# pcb-bldc-sensorless2.net
KiCad netlist of a schematic drawn in EAGLE
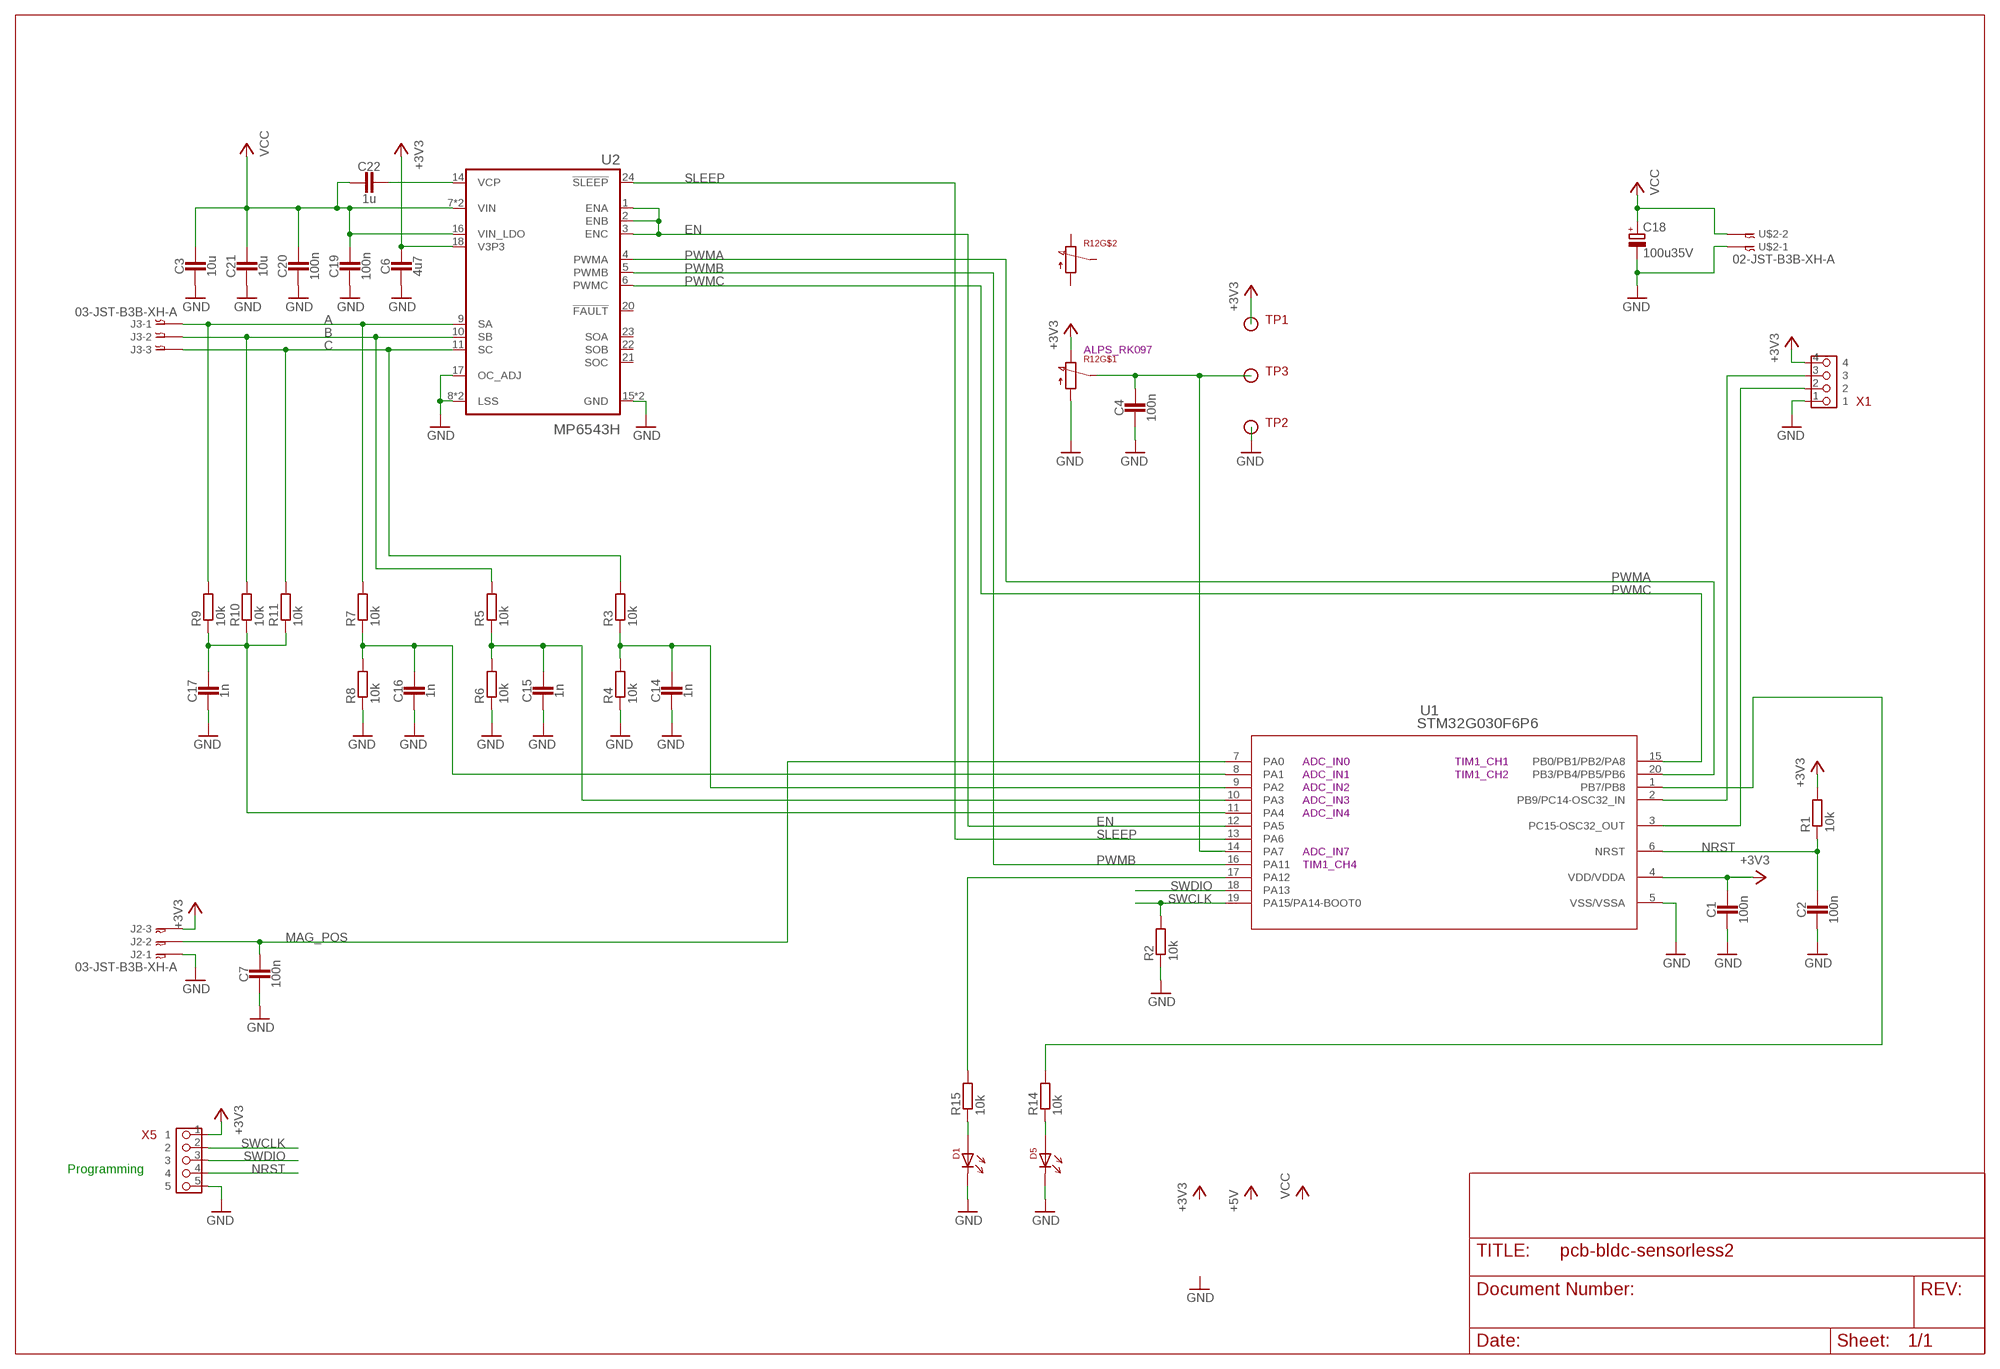
[diagram p0: schematic, sheet 1]

(export (version "E")
  (design (tool "Eeschema 10.0.6"))
  (components
    (comp (ref "C1")
      (value "100n")
      (footprint "eagle-import:0603_CAP")
      (libsource (lib "eagle-import") (part "CAPACITOR0603_CAP"))
    )
    (comp (ref "C2")
      (value "100n")
      (footprint "eagle-import:0603_CAP")
      (libsource (lib "eagle-import") (part "CAPACITOR0603_CAP"))
    )
    (comp (ref "C3")
      (value "10u")
      (footprint "eagle-import:1206_CAP")
      (libsource (lib "eagle-import") (part "CAPACITOR1206_CAP"))
    )
    (comp (ref "C4")
      (value "100n")
      (footprint "eagle-import:0603_CAP")
      (libsource (lib "eagle-import") (part "CAPACITOR0603_CAP"))
    )
    (comp (ref "C6")
      (value "4u7")
      (footprint "eagle-import:0805_CAP")
      (libsource (lib "eagle-import") (part "CAPACITOR0805_CAP"))
    )
    (comp (ref "C7")
      (value "100n")
      (footprint "eagle-import:0603_CAP")
      (libsource (lib "eagle-import") (part "CAPACITOR0603_CAP"))
    )
    (comp (ref "C14")
      (value "1n")
      (footprint "eagle-import:0603_CAP")
      (libsource (lib "eagle-import") (part "CAPACITOR0603_CAP"))
    )
    (comp (ref "C15")
      (value "1n")
      (footprint "eagle-import:0603_CAP")
      (libsource (lib "eagle-import") (part "CAPACITOR0603_CAP"))
    )
    (comp (ref "C16")
      (value "1n")
      (footprint "eagle-import:0603_CAP")
      (libsource (lib "eagle-import") (part "CAPACITOR0603_CAP"))
    )
    (comp (ref "C17")
      (value "1n")
      (footprint "eagle-import:0603_CAP")
      (libsource (lib "eagle-import") (part "CAPACITOR0603_CAP"))
    )
    (comp (ref "C18")
      (value "100u35V")
      (footprint "eagle-import:153CLV-0605")
      (libsource (lib "eagle-import") (part "CPOL-EU153CLV-0605"))
    )
    (comp (ref "C19")
      (value "100n")
      (footprint "eagle-import:0603_CAP")
      (libsource (lib "eagle-import") (part "CAPACITOR0603_CAP"))
    )
    (comp (ref "C20")
      (value "100n")
      (footprint "eagle-import:0603_CAP")
      (libsource (lib "eagle-import") (part "CAPACITOR0603_CAP"))
    )
    (comp (ref "C21")
      (value "10u")
      (footprint "eagle-import:1206_CAP")
      (libsource (lib "eagle-import") (part "CAPACITOR1206_CAP"))
    )
    (comp (ref "C22")
      (value "1u")
      (footprint "eagle-import:0603_CAP")
      (libsource (lib "eagle-import") (part "CAPACITOR0603_CAP"))
    )
    (comp (ref "D1")
      (value "LED-0805")
      (footprint "eagle-import:0805-DOT")
      (libsource (lib "eagle-import") (part "LED-0805"))
    )
    (comp (ref "D5")
      (value "LED-0805")
      (footprint "eagle-import:0805-DOT")
      (libsource (lib "eagle-import") (part "LED-0805"))
    )
    (comp (ref "J2")
      (value "03-JST-B3B-XH-A")
      (footprint "eagle-import:B3B-XH")
      (libsource (lib "eagle-import") (part "03-JST-B3B-XH-A"))
    )
    (comp (ref "J3")
      (value "03-JST-B3B-XH-A")
      (footprint "eagle-import:B3B-XH")
      (libsource (lib "eagle-import") (part "03-JST-B3B-XH-A"))
    )
    (comp (ref "R1")
      (value "10k")
      (footprint "eagle-import:0603-RES")
      (libsource (lib "eagle-import") (part "RESISTOR0603_RES"))
    )
    (comp (ref "R2")
      (value "10k")
      (footprint "eagle-import:0603-RES")
      (libsource (lib "eagle-import") (part "RESISTOR0603_RES"))
    )
    (comp (ref "R3")
      (value "10k")
      (footprint "eagle-import:0603-RES")
      (libsource (lib "eagle-import") (part "RESISTOR0603_RES"))
    )
    (comp (ref "R4")
      (value "10k")
      (footprint "eagle-import:0603-RES")
      (libsource (lib "eagle-import") (part "RESISTOR0603_RES"))
    )
    (comp (ref "R5")
      (value "10k")
      (footprint "eagle-import:0603-RES")
      (libsource (lib "eagle-import") (part "RESISTOR0603_RES"))
    )
    (comp (ref "R6")
      (value "10k")
      (footprint "eagle-import:0603-RES")
      (libsource (lib "eagle-import") (part "RESISTOR0603_RES"))
    )
    (comp (ref "R7")
      (value "10k")
      (footprint "eagle-import:0603-RES")
      (libsource (lib "eagle-import") (part "RESISTOR0603_RES"))
    )
    (comp (ref "R8")
      (value "10k")
      (footprint "eagle-import:0603-RES")
      (libsource (lib "eagle-import") (part "RESISTOR0603_RES"))
    )
    (comp (ref "R9")
      (value "10k")
      (footprint "eagle-import:0603-RES")
      (libsource (lib "eagle-import") (part "RESISTOR0603_RES"))
    )
    (comp (ref "R10")
      (value "10k")
      (footprint "eagle-import:0603-RES")
      (libsource (lib "eagle-import") (part "RESISTOR0603_RES"))
    )
    (comp (ref "R11")
      (value "10k")
      (footprint "eagle-import:0603-RES")
      (libsource (lib "eagle-import") (part "RESISTOR0603_RES"))
    )
    (comp (ref "R12")
      (value "POTDUAL")
      (footprint "eagle-import:ALPS_RK097")
      (libsource (lib "eagle-import") (part "POTDUAL"))
    )
    (comp (ref "R14")
      (value "10k")
      (footprint "eagle-import:0603-RES")
      (libsource (lib "eagle-import") (part "RESISTOR0603_RES"))
    )
    (comp (ref "R15")
      (value "10k")
      (footprint "eagle-import:0603-RES")
      (libsource (lib "eagle-import") (part "RESISTOR0603_RES"))
    )
    (comp (ref "TP1")
      (value "TESTPIN")
      (footprint "eagle-import:PIN-SMD-1X1-TEST_1M5")
      (libsource (lib "eagle-import") (part "TESTPIN"))
    )
    (comp (ref "TP2")
      (value "TESTPIN")
      (footprint "eagle-import:PIN-SMD-1X1-TEST_1M5")
      (libsource (lib "eagle-import") (part "TESTPIN"))
    )
    (comp (ref "TP3")
      (value "TESTPIN")
      (footprint "eagle-import:PIN-SMD-1X1-TEST_1M5")
      (libsource (lib "eagle-import") (part "TESTPIN"))
    )
    (comp (ref "U$2")
      (value "02-JST-B3B-XH-A")
      (footprint "eagle-import:B2B-XH")
      (libsource (lib "eagle-import") (part "02-JST-B3B-XH-A"))
    )
    (comp (ref "U1")
      (value "STM32G030F6P6")
      (footprint "eagle-import:TSSOP20")
      (fields (field (name "COPYRIGHT") "Copyright (C) 2024 Ultra Librarian. All rights reserved."))
      (libsource (lib "eagle-import") (part "STM32G030F6P6"))
    )
    (comp (ref "U2")
      (value "MP6543H")
      (footprint "eagle-import:QFN24")
      (libsource (lib "eagle-import") (part "MP6543H"))
    )
    (comp (ref "X1")
      (value "PIN_4X1HD")
      (footprint "eagle-import:PIN_4X1_HD")
      (libsource (lib "eagle-import") (part "PIN_4X1HD"))
    )
    (comp (ref "X5")
      (value "PIN_5X1HD")
      (footprint "eagle-import:PIN_5X1_HD")
      (libsource (lib "eagle-import") (part "PIN_5X1HD"))
    )
  )
  (nets
    (net (code "1") (name "+3V3") (class "Default")
      (node (ref "C1") (pin "1") (pinfunction "1_1") (pintype "bidirectional"))
      (node (ref "C6") (pin "P$1") (pinfunction "1_P$1") (pintype "bidirectional"))
      (node (ref "J2") (pin "P$3") (pinfunction "1_P$3") (pintype "passive"))
      (node (ref "R1") (pin "2") (pinfunction "2_2") (pintype "passive"))
      (node (ref "R12") (pin "R11") (pinfunction "1_R11") (pintype "bidirectional"))
      (node (ref "TP1") (pin "1") (pinfunction "1_1") (pintype "bidirectional"))
      (node (ref "U1") (pin "4") (pinfunction "VDD/VDDA_4") (pintype "power_in"))
      (node (ref "U2") (pin "18") (pinfunction "V3P3_18") (pintype "bidirectional"))
      (node (ref "X1") (pin "4") (pinfunction "4_4") (pintype "bidirectional"))
      (node (ref "X5") (pin "1") (pinfunction "1_1") (pintype "bidirectional"))
    )
    (net (code "3") (name "/A") (class "Default")
      (node (ref "J3") (pin "P$1") (pinfunction "1_P$1") (pintype "passive"))
      (node (ref "R7") (pin "2") (pinfunction "2_2") (pintype "passive"))
      (node (ref "R9") (pin "2") (pinfunction "2_2") (pintype "passive"))
      (node (ref "U2") (pin "9") (pinfunction "SA_9") (pintype "bidirectional"))
    )
    (net (code "4") (name "/B") (class "Default")
      (node (ref "J3") (pin "P$2") (pinfunction "1_P$2") (pintype "passive"))
      (node (ref "R10") (pin "2") (pinfunction "2_2") (pintype "passive"))
      (node (ref "R5") (pin "2") (pinfunction "2_2") (pintype "passive"))
      (node (ref "U2") (pin "10") (pinfunction "SB_10") (pintype "bidirectional"))
    )
    (net (code "5") (name "/C") (class "Default")
      (node (ref "J3") (pin "P$3") (pinfunction "1_P$3") (pintype "passive"))
      (node (ref "R11") (pin "2") (pinfunction "2_2") (pintype "passive"))
      (node (ref "R3") (pin "2") (pinfunction "2_2") (pintype "passive"))
      (node (ref "U2") (pin "11") (pinfunction "SC_11") (pintype "bidirectional"))
    )
    (net (code "6") (name "/EN") (class "Default")
      (node (ref "U1") (pin "12") (pinfunction "PA5_12") (pintype "bidirectional"))
      (node (ref "U2") (pin "1") (pinfunction "ENA_1") (pintype "bidirectional"))
      (node (ref "U2") (pin "2") (pinfunction "ENB_2") (pintype "bidirectional"))
      (node (ref "U2") (pin "3") (pinfunction "ENC_3") (pintype "bidirectional"))
    )
    (net (code "7") (name "/MAG_POS") (class "Default")
      (node (ref "C7") (pin "1") (pinfunction "1_1") (pintype "bidirectional"))
      (node (ref "J2") (pin "P$2") (pinfunction "1_P$2") (pintype "passive"))
      (node (ref "U1") (pin "7") (pinfunction "PA0_7") (pintype "bidirectional"))
    )
    (net (code "8") (name "/NRST") (class "Default")
      (node (ref "C2") (pin "1") (pinfunction "1_1") (pintype "bidirectional"))
      (node (ref "R1") (pin "1") (pinfunction "1_1") (pintype "passive"))
      (node (ref "U1") (pin "6") (pinfunction "NRST_6") (pintype "bidirectional"))
      (node (ref "X5") (pin "4") (pinfunction "4_4") (pintype "bidirectional"))
    )
    (net (code "9") (name "/PWMA") (class "Default")
      (node (ref "U1") (pin "20") (pinfunction "PB3/PB4/PB5/PB6_20") (pintype "bidirectional"))
      (node (ref "U2") (pin "4") (pinfunction "PWMA_4") (pintype "bidirectional"))
    )
    (net (code "10") (name "/PWMB") (class "Default")
      (node (ref "U1") (pin "16") (pinfunction "PA11_16") (pintype "bidirectional"))
      (node (ref "U2") (pin "5") (pinfunction "PWMB_5") (pintype "bidirectional"))
    )
    (net (code "11") (name "/PWMC") (class "Default")
      (node (ref "U1") (pin "15") (pinfunction "PB0/PB1/PB2/PA8_15") (pintype "bidirectional"))
      (node (ref "U2") (pin "6") (pinfunction "PWMC_6") (pintype "bidirectional"))
    )
    (net (code "12") (name "/SLEEP") (class "Default")
      (node (ref "U1") (pin "13") (pinfunction "PA6_13") (pintype "bidirectional"))
      (node (ref "U2") (pin "24") (pinfunction "~{SLEEP}_24") (pintype "bidirectional"))
    )
    (net (code "13") (name "/SWCLK") (class "Default")
      (node (ref "R2") (pin "2") (pinfunction "2_2") (pintype "passive"))
      (node (ref "U1") (pin "19") (pinfunction "PA15/PA14-BOOT0_19") (pintype "bidirectional"))
      (node (ref "X5") (pin "2") (pinfunction "2_2") (pintype "bidirectional"))
    )
    (net (code "14") (name "/SWDIO") (class "Default")
      (node (ref "U1") (pin "18") (pinfunction "PA13_18") (pintype "bidirectional"))
      (node (ref "X5") (pin "3") (pinfunction "3_3") (pintype "bidirectional"))
    )
    (net (code "15") (name "GND") (class "Default")
      (node (ref "C1") (pin "2") (pinfunction "2_2") (pintype "bidirectional"))
      (node (ref "C14") (pin "2") (pinfunction "2_2") (pintype "bidirectional"))
      (node (ref "C15") (pin "2") (pinfunction "2_2") (pintype "bidirectional"))
      (node (ref "C16") (pin "2") (pinfunction "2_2") (pintype "bidirectional"))
      (node (ref "C17") (pin "2") (pinfunction "2_2") (pintype "bidirectional"))
      (node (ref "C18") (pin "-") (pinfunction "-_-") (pintype "passive"))
      (node (ref "C19") (pin "2") (pinfunction "2_2") (pintype "bidirectional"))
      (node (ref "C2") (pin "2") (pinfunction "2_2") (pintype "bidirectional"))
      (node (ref "C20") (pin "2") (pinfunction "2_2") (pintype "bidirectional"))
      (node (ref "C21") (pin "2") (pinfunction "2_2") (pintype "bidirectional"))
      (node (ref "C3") (pin "2") (pinfunction "2_2") (pintype "bidirectional"))
      (node (ref "C4") (pin "2") (pinfunction "2_2") (pintype "bidirectional"))
      (node (ref "C6") (pin "P$2") (pinfunction "2_P$2") (pintype "bidirectional"))
      (node (ref "C7") (pin "2") (pinfunction "2_2") (pintype "bidirectional"))
      (node (ref "D1") (pin "2") (pinfunction "2_2") (pintype "bidirectional"))
      (node (ref "D5") (pin "2") (pinfunction "2_2") (pintype "bidirectional"))
      (node (ref "J2") (pin "P$1") (pinfunction "1_P$1") (pintype "passive"))
      (node (ref "R12") (pin "R13") (pinfunction "3_R13") (pintype "bidirectional"))
      (node (ref "R2") (pin "1") (pinfunction "1_1") (pintype "passive"))
      (node (ref "R4") (pin "1") (pinfunction "1_1") (pintype "passive"))
      (node (ref "R6") (pin "1") (pinfunction "1_1") (pintype "passive"))
      (node (ref "R8") (pin "1") (pinfunction "1_1") (pintype "passive"))
      (node (ref "TP2") (pin "1") (pinfunction "1_1") (pintype "bidirectional"))
      (node (ref "U$2") (pin "P$1") (pinfunction "1_P$1") (pintype "passive"))
      (node (ref "U1") (pin "5") (pinfunction "VSS/VSSA_5") (pintype "power_in"))
      (node (ref "U2") (pin "12") (pinfunction "LSS_12") (pintype "bidirectional"))
      (node (ref "U2") (pin "15") (pinfunction "GND_15") (pintype "bidirectional"))
      (node (ref "U2") (pin "17") (pinfunction "OC_ADJ_17") (pintype "bidirectional"))
      (node (ref "U2") (pin "25") (pinfunction "GND_25") (pintype "bidirectional"))
      (node (ref "U2") (pin "8") (pinfunction "LSS_8") (pintype "bidirectional"))
      (node (ref "X1") (pin "1") (pinfunction "1_1") (pintype "bidirectional"))
      (node (ref "X5") (pin "5") (pinfunction "5_5") (pintype "bidirectional"))
    )
    (net (code "16") (name "Net-(D1-Pad1)") (class "Default")
      (node (ref "D1") (pin "1") (pinfunction "1_1") (pintype "bidirectional"))
      (node (ref "R15") (pin "1") (pinfunction "1_1") (pintype "passive"))
    )
    (net (code "17") (name "Net-(D5-Pad1)") (class "Default")
      (node (ref "D5") (pin "1") (pinfunction "1_1") (pintype "bidirectional"))
      (node (ref "R14") (pin "1") (pinfunction "1_1") (pintype "passive"))
    )
    (net (code "18") (name "Net-(R12A-2)") (class "Default")
      (node (ref "C4") (pin "1") (pinfunction "1_1") (pintype "bidirectional"))
      (node (ref "R12") (pin "R12") (pinfunction "2_R12") (pintype "bidirectional"))
      (node (ref "TP3") (pin "1") (pinfunction "1_1") (pintype "bidirectional"))
      (node (ref "U1") (pin "14") (pinfunction "PA7_14") (pintype "bidirectional"))
    )
    (net (code "19") (name "Net-(U1-PA1)") (class "Default")
      (node (ref "C16") (pin "1") (pinfunction "1_1") (pintype "bidirectional"))
      (node (ref "R7") (pin "1") (pinfunction "1_1") (pintype "passive"))
      (node (ref "R8") (pin "2") (pinfunction "2_2") (pintype "passive"))
      (node (ref "U1") (pin "8") (pinfunction "PA1_8") (pintype "bidirectional"))
    )
    (net (code "20") (name "Net-(U1-PA2)") (class "Default")
      (node (ref "C14") (pin "1") (pinfunction "1_1") (pintype "bidirectional"))
      (node (ref "R3") (pin "1") (pinfunction "1_1") (pintype "passive"))
      (node (ref "R4") (pin "2") (pinfunction "2_2") (pintype "passive"))
      (node (ref "U1") (pin "9") (pinfunction "PA2_9") (pintype "bidirectional"))
    )
    (net (code "21") (name "Net-(U1-PA3)") (class "Default")
      (node (ref "C15") (pin "1") (pinfunction "1_1") (pintype "bidirectional"))
      (node (ref "R5") (pin "1") (pinfunction "1_1") (pintype "passive"))
      (node (ref "R6") (pin "2") (pinfunction "2_2") (pintype "passive"))
      (node (ref "U1") (pin "10") (pinfunction "PA3_10") (pintype "bidirectional"))
    )
    (net (code "22") (name "Net-(U1-PA4)") (class "Default")
      (node (ref "C17") (pin "1") (pinfunction "1_1") (pintype "bidirectional"))
      (node (ref "R10") (pin "1") (pinfunction "1_1") (pintype "passive"))
      (node (ref "R11") (pin "1") (pinfunction "1_1") (pintype "passive"))
      (node (ref "R9") (pin "1") (pinfunction "1_1") (pintype "passive"))
      (node (ref "U1") (pin "11") (pinfunction "PA4_11") (pintype "bidirectional"))
    )
    (net (code "23") (name "Net-(U1-PA12)") (class "Default")
      (node (ref "R15") (pin "2") (pinfunction "2_2") (pintype "passive"))
      (node (ref "U1") (pin "17") (pinfunction "PA12_17") (pintype "bidirectional"))
    )
    (net (code "24") (name "Net-(U1-PB7{slash}PB8)") (class "Default")
      (node (ref "R14") (pin "2") (pinfunction "2_2") (pintype "passive"))
      (node (ref "U1") (pin "1") (pinfunction "PB7/PB8_1") (pintype "bidirectional"))
    )
    (net (code "25") (name "Net-(U1-PB9{slash}PC14-OSC32_IN)") (class "Default")
      (node (ref "U1") (pin "2") (pinfunction "PB9/PC14-OSC32_IN_2") (pintype "bidirectional"))
      (node (ref "X1") (pin "3") (pinfunction "3_3") (pintype "bidirectional"))
    )
    (net (code "26") (name "Net-(U1-PC15-OSC32_OUT)") (class "Default")
      (node (ref "U1") (pin "3") (pinfunction "PC15-OSC32_OUT_3") (pintype "bidirectional"))
      (node (ref "X1") (pin "2") (pinfunction "2_2") (pintype "bidirectional"))
    )
    (net (code "27") (name "Net-(U2-VCP)") (class "Default")
      (node (ref "C22") (pin "1") (pinfunction "1_1") (pintype "bidirectional"))
      (node (ref "U2") (pin "14") (pinfunction "VCP_14") (pintype "bidirectional"))
    )
    (net (code "28") (name "VCC") (class "Default")
      (node (ref "C18") (pin "+") (pinfunction "+_+") (pintype "passive"))
      (node (ref "C19") (pin "1") (pinfunction "1_1") (pintype "bidirectional"))
      (node (ref "C20") (pin "1") (pinfunction "1_1") (pintype "bidirectional"))
      (node (ref "C21") (pin "1") (pinfunction "1_1") (pintype "bidirectional"))
      (node (ref "C22") (pin "2") (pinfunction "2_2") (pintype "bidirectional"))
      (node (ref "C3") (pin "1") (pinfunction "1_1") (pintype "bidirectional"))
      (node (ref "U$2") (pin "P$2") (pinfunction "1_P$2") (pintype "passive"))
      (node (ref "U2") (pin "13") (pinfunction "VIN_13") (pintype "bidirectional"))
      (node (ref "U2") (pin "16") (pinfunction "VIN_LDO_16") (pintype "bidirectional"))
      (node (ref "U2") (pin "7") (pinfunction "VIN_7") (pintype "bidirectional"))
    )
    (net (code "29") (name "unconnected-(R12B-1-PadR21)") (class "Default")
      (node (ref "R12") (pin "R21") (pinfunction "1_R21") (pintype "bidirectional"))
    )
    (net (code "30") (name "unconnected-(R12B-2-PadR22)") (class "Default")
      (node (ref "R12") (pin "R22") (pinfunction "2_R22") (pintype "bidirectional"))
    )
    (net (code "31") (name "unconnected-(R12B-3-PadR23)") (class "Default")
      (node (ref "R12") (pin "R23") (pinfunction "3_R23") (pintype "bidirectional"))
    )
    (net (code "32") (name "unconnected-(U2-SOA-Pad23)") (class "Default")
      (node (ref "U2") (pin "23") (pinfunction "SOA_23") (pintype "bidirectional"))
    )
    (net (code "33") (name "unconnected-(U2-SOB-Pad22)") (class "Default")
      (node (ref "U2") (pin "22") (pinfunction "SOB_22") (pintype "bidirectional"))
    )
    (net (code "34") (name "unconnected-(U2-SOC-Pad21)") (class "Default")
      (node (ref "U2") (pin "21") (pinfunction "SOC_21") (pintype "bidirectional"))
    )
    (net (code "35") (name "unconnected-(U2-~{FAULT}-Pad20)") (class "Default")
      (node (ref "U2") (pin "20") (pinfunction "~{FAULT}_20") (pintype "bidirectional"))
    )
  )
)
